# SheetMSP.net
KiCad netlist of a schematic drawn in Altium Designer
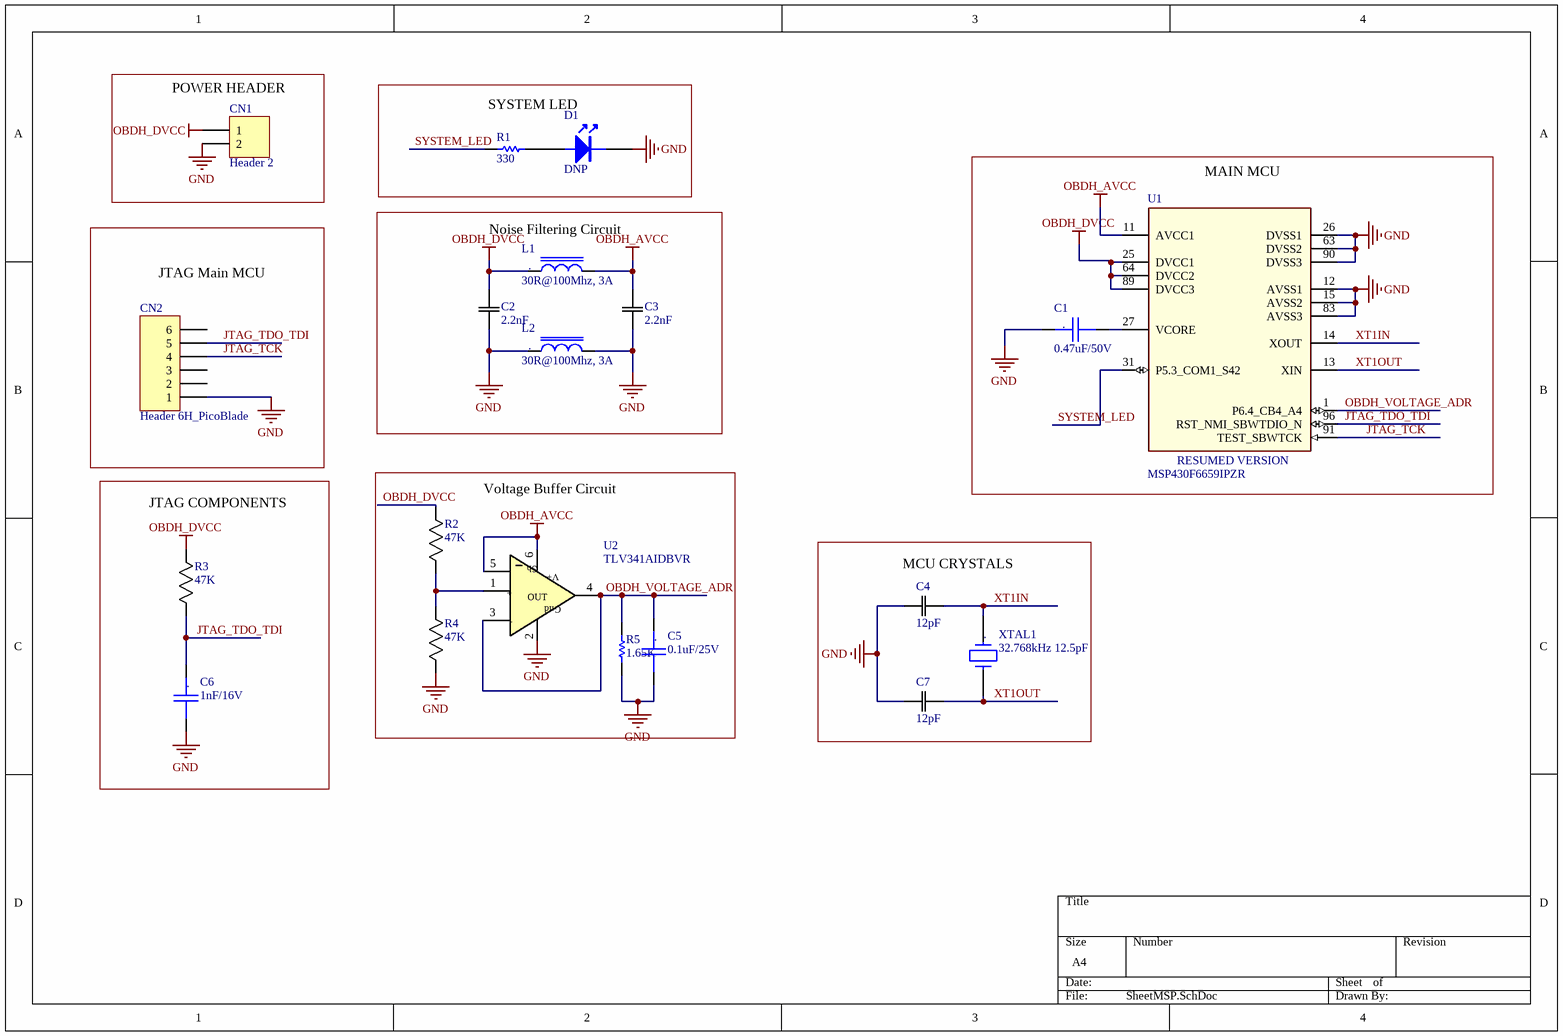
[diagram p0: SheetMSP.SchDoc]

(export (version "E")
  (design (tool "Eeschema 10.0.6"))
  (components
    (comp (ref "C1")
      (value "0.47uF/50V")
      (footprint "C0805_MD")
      (description "CAP CER 0.47UF 50V 10% X7R 0805")
      (fields (field (name "PARTNUMBER") "C0805C474K5RACTU"))
      (libsource (lib "MPS430_Task") (part "Cap_Cer_X7R_0.47uF_50V_0805"))
    )
    (comp (ref "C2")
      (value "2.2nF")
      (footprint "C0402_MD")
      (description "Imported")
      (fields
        (field (name "MANUFACTURER_PART_NUMBER") "GRM155R71C222KA01D")
        (field (name "MANUFACTURER") "Murata")
      )
      (libsource (lib "MPS430_Task") (part "Cap 2.2nF/16V_0402"))
    )
    (comp (ref "C3")
      (value "2.2nF")
      (footprint "C0402_MD")
      (description "Imported")
      (fields
        (field (name "MANUFACTURER_PART_NUMBER") "GRM155R71C222KA01D")
        (field (name "MANUFACTURER") "Murata")
      )
      (libsource (lib "MPS430_Task") (part "Cap 2.2nF/16V_0402"))
    )
    (comp (ref "C4")
      (value "12pF")
      (footprint "GRM1555C1H120JA01J")
      (description "Multilayer Ceramic Capacitors MLCC - SMD/SMT 0402 12pF 50volts C0G 5%")
      (fields
        (field (name "MANUFACTURER") "Murata")
        (field (name "MANUFACTURER PART NUMBER") "GRM1555C1H120JA01J")
      )
      (libsource (lib "MPS430_Task") (part "GRM1555C1H120JA01J"))
    )
    (comp (ref "C5")
      (value "0.1uF/25V")
      (footprint "C0805_MD")
      (description "CAP CER 0.1UF 25V 10% X7R 0805")
      (fields (field (name "PARTNUMBER") "CC0805KRX7R8BB104"))
      (libsource (lib "MPS430_Task") (part "Cap_Cer_X7R_0.1uF_25V_0805"))
    )
    (comp (ref "C6")
      (value "1nF/16V")
      (footprint "C0603_MD")
      (description "CAP CER 1nF 16V 0603 5%")
      (fields (field (name "PARTNUMBER") "C0603X102J4RECAUTO"))
      (libsource (lib "MPS430_Task") (part "Cap_Cer_X7R_1nF_16V_0603"))
    )
    (comp (ref "C7")
      (value "12pF")
      (footprint "GRM1555C1H120JA01J")
      (description "Multilayer Ceramic Capacitors MLCC - SMD/SMT 0402 12pF 50volts C0G 5%")
      (fields
        (field (name "MANUFACTURER") "Murata")
        (field (name "MANUFACTURER PART NUMBER") "GRM1555C1H120JA01J")
      )
      (libsource (lib "MPS430_Task") (part "GRM1555C1H120JA01J"))
    )
    (comp (ref "CN1")
      (value "Header 2")
      (footprint "HEADER 2M 2.54mm 180 GRAUS")
      (description "Header, 2-Pin")
      (fields (field (name "PARTNUMBER") "826646-2") (field (name "PUBLISHER") "Altium Limited"))
      (libsource (lib "MPS430_Task") (part "Header 2"))
    )
    (comp (ref "CN2")
      (value "Header 6H_PicoBlade")
      (footprint "PICO BLADE 0532610671")
      (description "Header, 6-Pin, Right Angle")
      (fields (field (name "PARTNUMBER") "53398-0671") (field (name "PUBLISHER") "Altium Limited"))
      (libsource (lib "MPS430_Task") (part "Header 6H_PicoBlade"))
    )
    (comp (ref "D1")
      (value "DNP")
      (footprint "L0805 GREEN")
      (description "SMD Green LED")
      (fields (field (name "PARTNUMBER") "LTST-C171GKT"))
      (libsource (lib "MPS430_Task") (part "LED/G_0805"))
    )
    (comp (ref "L1")
      (value "30R@100Mhz, 3A")
      (footprint "L0805")
      (description "Ferrite Bead 30 OHM 3A 100MHz")
      (fields (field (name "PARTNUMBER") "BLM21PG300SN1D"))
      (libsource (lib "MPS430_Task") (part "FB_30R_3A_100MHz_0805"))
    )
    (comp (ref "L2")
      (value "30R@100Mhz, 3A")
      (footprint "L0805")
      (description "Ferrite Bead 30 OHM 3A 100MHz")
      (fields (field (name "PARTNUMBER") "BLM21PG300SN1D"))
      (libsource (lib "MPS430_Task") (part "FB_30R_3A_100MHz_0805"))
    )
    (comp (ref "R1")
      (value "330")
      (footprint "R0603_MD")
      (fields
        (field (name "MANUFACTURER") "Vishay")
        (field (name "MANUFACTURER PART NUMBER") "CRCW0603330RFKEAHP")
        (field (name "TOLERANCE") "1%")
      )
      (libsource (lib "MPS430_Task") (part "Resistor 330"))
    )
    (comp (ref "R2")
      (value "47K")
      (footprint "R0805_MD")
      (description "Imported")
      (fields
        (field (name "MANUFACTURER_PART_NUMBER") "ERA-6AEB473V")
        (field (name "MANUFACTURER") "Panasonic ECG")
      )
      (libsource (lib "MPS430_Task") (part "Resistor 47 Kohms"))
    )
    (comp (ref "R3")
      (value "47K")
      (footprint "R0805_MD")
      (description "Imported")
      (fields
        (field (name "MANUFACTURER_PART_NUMBER") "ERA-6AEB473V")
        (field (name "MANUFACTURER") "Panasonic ECG")
      )
      (libsource (lib "MPS430_Task") (part "Resistor 47 Kohms"))
    )
    (comp (ref "R4")
      (value "47K")
      (footprint "R0805_MD")
      (description "Imported")
      (fields
        (field (name "MANUFACTURER_PART_NUMBER") "ERA-6AEB473V")
        (field (name "MANUFACTURER") "Panasonic ECG")
      )
      (libsource (lib "MPS430_Task") (part "Resistor 47 Kohms"))
    )
    (comp (ref "R5")
      (value "1.65K")
      (footprint "R0805_MD")
      (description "RES 1.65K OHM 1/10W 0.1% 0805")
      (fields (field (name "PARTNUMBER") "PCF0805R-1K65BT1"))
      (libsource (lib "MPS430_Task") (part "R1.65K_1%_1/10W_0805"))
    )
    (comp (ref "U1")
      (value "MSP430F6659IPZR")
      (footprint "PZ0100A_N")
      (fields (field (name "MANUFACTURER") "Texas Instruments"))
      (libsource (lib "MPS430_Task") (part "MSP430F6659IPZR"))
    )
    (comp (ref "U2")
      (value "TLV341AIDBVR")
      (footprint "SOT-23 6L")
      (libsource (lib "MPS430_Task") (part "TLV341AIDBVR"))
    )
    (comp (ref "XTAL1")
      (value "32.768kHz 12.5pF")
      (footprint "ABS06 0805")
      (description "32.768kHz ±20ppm Crystal 12.5pF 70 kOhm -40°C ~ 125°C")
      (fields (field (name "PARTNUMBER") "ECS-.327-12.5-34S-TR"))
      (libsource (lib "MPS430_Task") (part "Xtal_32.768kHz_12pF_2_SMD"))
    )
  )
  (nets
    (net (code "1") (name "/JTAG_TCK") (class "Default")
      (node (ref "CN2") (pin "4") (pinfunction "4_4") (pintype "passive"))
      (node (ref "U1") (pin "91") (pinfunction "TEST_SBWTCK_91") (pintype "input"))
    )
    (net (code "2") (name "/JTAG_TDO_TDI") (class "Default")
      (node (ref "C6") (pin "1") (pinfunction "1_1") (pintype "passive"))
      (node (ref "CN2") (pin "5") (pinfunction "5_5") (pintype "passive"))
      (node (ref "R3") (pin "2") (pinfunction "2_2") (pintype "passive"))
      (node (ref "U1") (pin "96") (pinfunction "RST_NMI_SBWTDIO_N_96") (pintype "bidirectional"))
    )
    (net (code "3") (name "/OBDH_VOLTAGE_ADR") (class "Default")
      (node (ref "C5") (pin "1") (pinfunction "1_1") (pintype "passive"))
      (node (ref "R5") (pin "2") (pinfunction "2_2") (pintype "passive"))
      (node (ref "U1") (pin "1") (pinfunction "P6.4_CB4_A4_1") (pintype "bidirectional"))
      (node (ref "U2") (pin "3") (pinfunction "-IN_3") (pintype "passive"))
      (node (ref "U2") (pin "4") (pinfunction "OUT_4") (pintype "passive"))
    )
    (net (code "4") (name "/SYSTEM_LED") (class "Default")
      (node (ref "R1") (pin "2") (pinfunction "2_2") (pintype "passive"))
      (node (ref "U1") (pin "31") (pinfunction "P5.3_COM1_S42_31") (pintype "bidirectional"))
    )
    (net (code "5") (name "/XT1IN") (class "Default")
      (node (ref "C4") (pin "2") (pinfunction "2_2") (pintype "passive"))
      (node (ref "U1") (pin "14") (pinfunction "XOUT_14") (pintype "passive"))
      (node (ref "XTAL1") (pin "1") (pinfunction "1_1") (pintype "passive"))
    )
    (net (code "6") (name "/XT1OUT") (class "Default")
      (node (ref "C7") (pin "2") (pinfunction "2_2") (pintype "passive"))
      (node (ref "U1") (pin "13") (pinfunction "XIN_13") (pintype "passive"))
      (node (ref "XTAL1") (pin "2") (pinfunction "2_2") (pintype "passive"))
    )
    (net (code "7") (name "GND") (class "Default")
      (node (ref "C1") (pin "1") (pinfunction "1_1") (pintype "passive"))
      (node (ref "C2") (pin "1") (pinfunction "1_1") (pintype "passive"))
      (node (ref "C3") (pin "1") (pinfunction "1_1") (pintype "passive"))
      (node (ref "C4") (pin "1") (pinfunction "1_1") (pintype "passive"))
      (node (ref "C5") (pin "2") (pinfunction "2_2") (pintype "passive"))
      (node (ref "C6") (pin "2") (pinfunction "2_2") (pintype "passive"))
      (node (ref "C7") (pin "1") (pinfunction "1_1") (pintype "passive"))
      (node (ref "CN1") (pin "2") (pinfunction "2_2") (pintype "passive"))
      (node (ref "CN2") (pin "1") (pinfunction "1_1") (pintype "passive"))
      (node (ref "D1") (pin "K") (pinfunction "K_K") (pintype "passive"))
      (node (ref "L2") (pin "1") (pinfunction "1_1") (pintype "passive"))
      (node (ref "L2") (pin "2") (pinfunction "2_2") (pintype "passive"))
      (node (ref "R4") (pin "2") (pinfunction "2_2") (pintype "passive"))
      (node (ref "R5") (pin "1") (pinfunction "1_1") (pintype "passive"))
      (node (ref "U1") (pin "12") (pinfunction "AVSS1_12") (pintype "power_in"))
      (node (ref "U1") (pin "15") (pinfunction "AVSS2_15") (pintype "power_in"))
      (node (ref "U1") (pin "26") (pinfunction "DVSS1_26") (pintype "passive"))
      (node (ref "U1") (pin "63") (pinfunction "DVSS2_63") (pintype "power_in"))
      (node (ref "U1") (pin "83") (pinfunction "AVSS3_83") (pintype "power_in"))
      (node (ref "U1") (pin "90") (pinfunction "DVSS3_90") (pintype "passive"))
      (node (ref "U2") (pin "2") (pinfunction "Gnd_2") (pintype "passive"))
    )
    (net (code "8") (name "Net-(D1-PadA)") (class "Default")
      (node (ref "D1") (pin "A") (pinfunction "A_A") (pintype "passive"))
      (node (ref "R1") (pin "1") (pinfunction "1_1") (pintype "passive"))
    )
    (net (code "9") (name "Net-(U1-VCORE)") (class "Default")
      (node (ref "C1") (pin "2") (pinfunction "2_2") (pintype "passive"))
      (node (ref "U1") (pin "27") (pinfunction "VCORE_27") (pintype "power_in"))
    )
    (net (code "10") (name "Net-(U2-+IN)") (class "Default")
      (node (ref "R2") (pin "2") (pinfunction "2_2") (pintype "passive"))
      (node (ref "R4") (pin "1") (pinfunction "1_1") (pintype "passive"))
      (node (ref "U2") (pin "1") (pinfunction "+IN_1") (pintype "passive"))
    )
    (net (code "11") (name "OBDH_AVCC") (class "Default")
      (node (ref "C3") (pin "2") (pinfunction "2_2") (pintype "passive"))
      (node (ref "L1") (pin "2") (pinfunction "2_2") (pintype "passive"))
      (node (ref "U1") (pin "11") (pinfunction "AVCC1_11") (pintype "power_in"))
      (node (ref "U2") (pin "5") (pinfunction "EN_5") (pintype "passive"))
      (node (ref "U2") (pin "6") (pinfunction "V+_6") (pintype "passive"))
    )
    (net (code "12") (name "OBDH_DVCC") (class "Default")
      (node (ref "C2") (pin "2") (pinfunction "2_2") (pintype "passive"))
      (node (ref "CN1") (pin "1") (pinfunction "1_1") (pintype "passive"))
      (node (ref "L1") (pin "1") (pinfunction "1_1") (pintype "passive"))
      (node (ref "R2") (pin "1") (pinfunction "1_1") (pintype "passive"))
      (node (ref "R3") (pin "1") (pinfunction "1_1") (pintype "passive"))
      (node (ref "U1") (pin "25") (pinfunction "DVCC1_25") (pintype "power_in"))
      (node (ref "U1") (pin "64") (pinfunction "DVCC2_64") (pintype "power_in"))
      (node (ref "U1") (pin "89") (pinfunction "DVCC3_89") (pintype "power_in"))
    )
    (net (code "13") (name "unconnected-(CN2-Pad2)") (class "Default")
      (node (ref "CN2") (pin "2") (pinfunction "2_2") (pintype "passive"))
    )
    (net (code "14") (name "unconnected-(CN2-Pad3)") (class "Default")
      (node (ref "CN2") (pin "3") (pinfunction "3_3") (pintype "passive"))
    )
    (net (code "15") (name "unconnected-(CN2-Pad6)") (class "Default")
      (node (ref "CN2") (pin "6") (pinfunction "6_6") (pintype "passive"))
    )
  )
)
